# Sheet5.net
KiCad netlist of a schematic drawn in Altium Designer
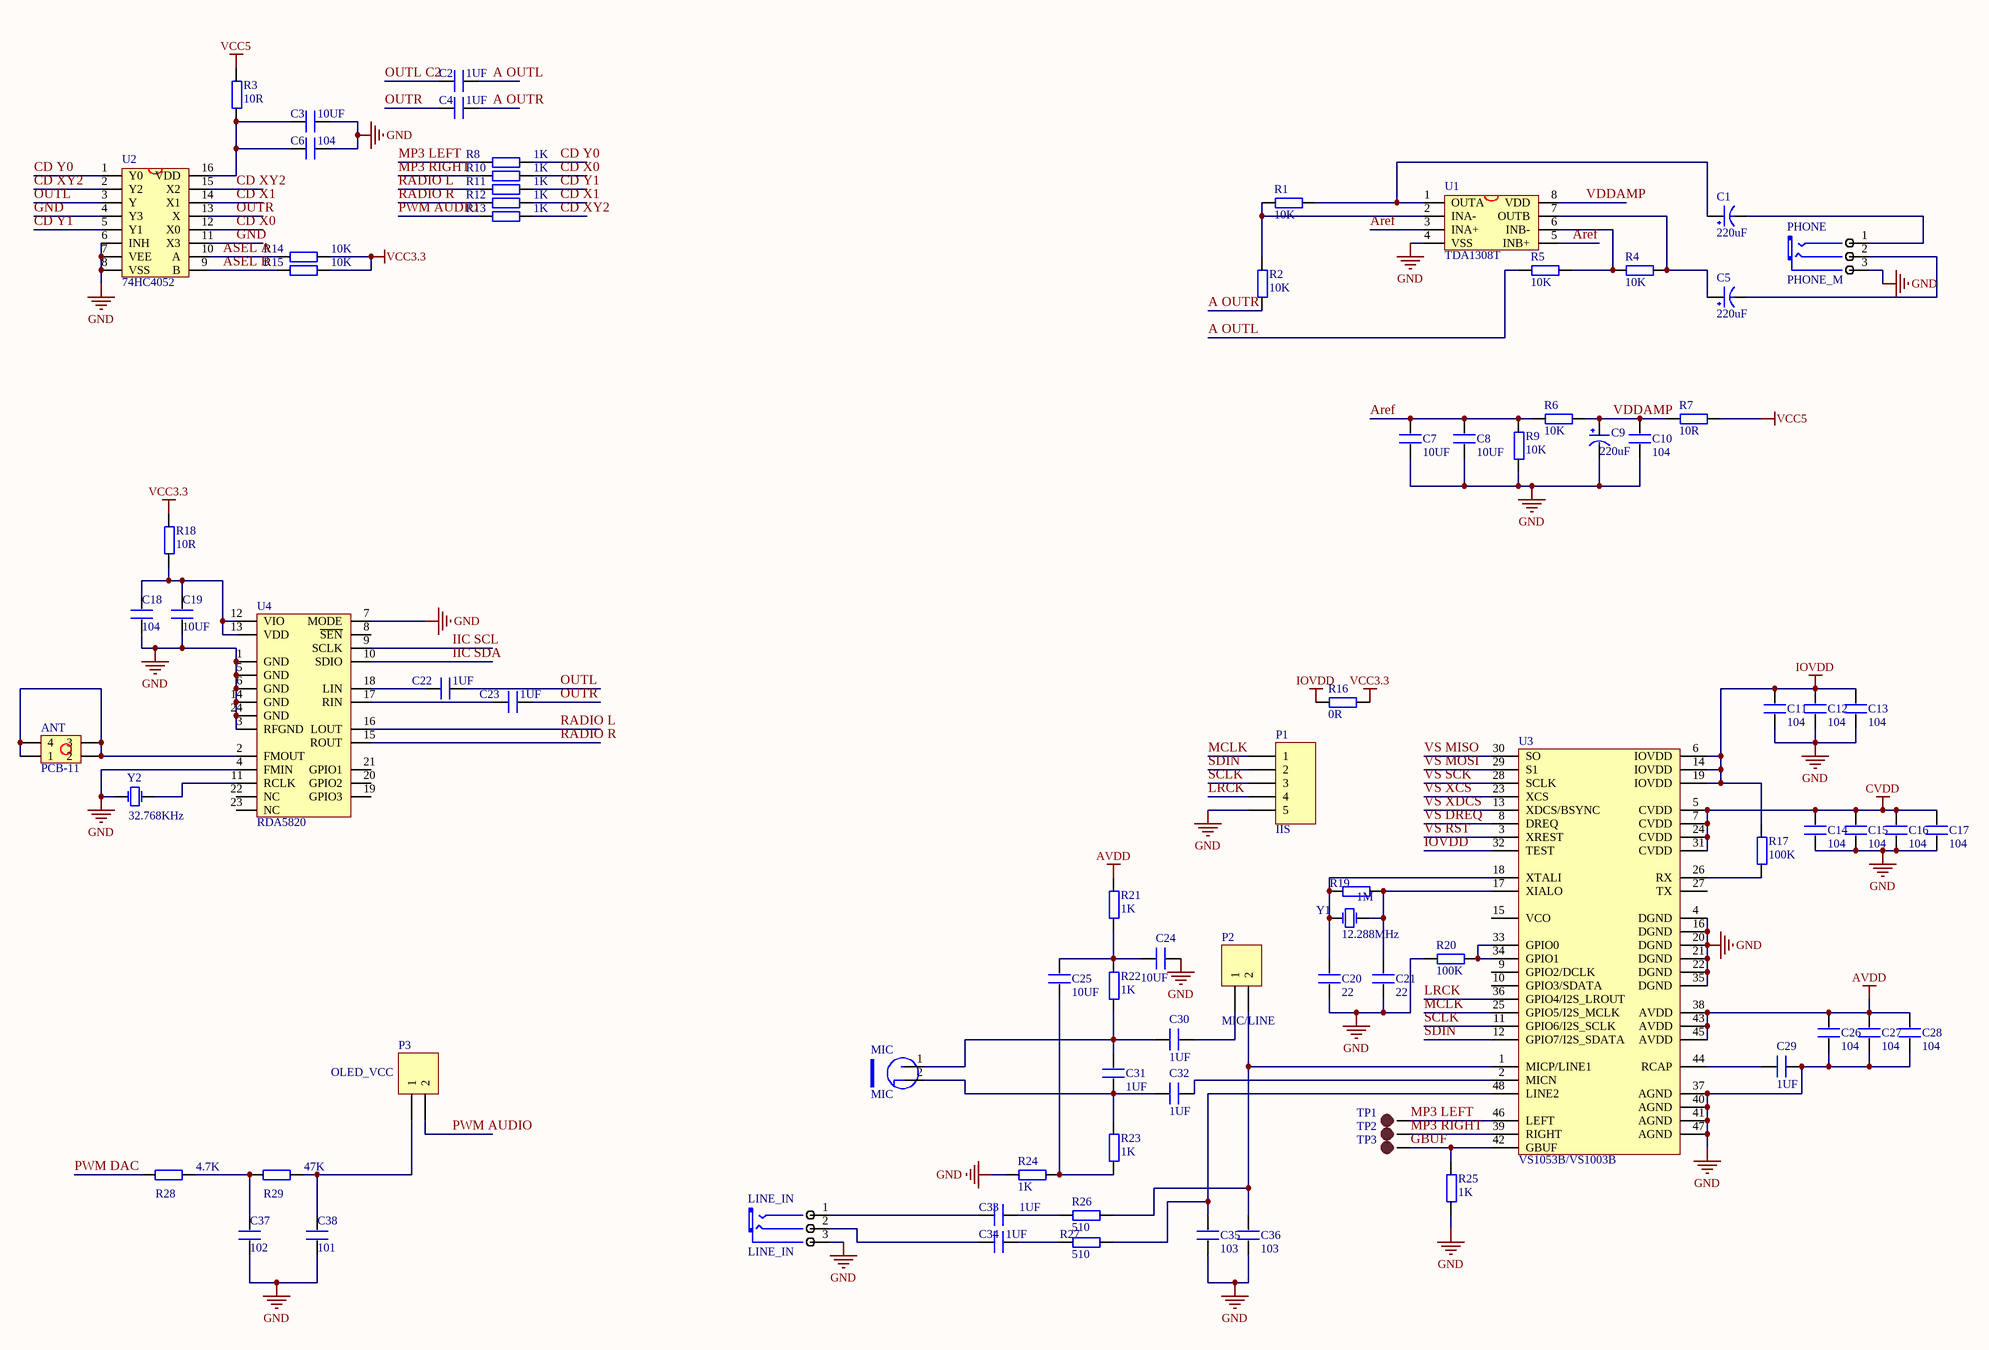
[diagram p0: Sheet5.SchDoc]

(export (version "E")
  (design (tool "Eeschema 10.0.6"))
  (components
    (comp (ref "ANT")
      (value "PCB-11")
      (footprint "PCB-11")
      (description "PCB接线端子")
      (libsource (lib "战舰STM32开发板底板封装库") (part "PCB-11"))
    )
    (comp (ref "C1") (value "220uF") (footprint "CC6.56.5") (libsource (lib "战舰STM32开发板底板封装库") (part "CAP")))
    (comp (ref "C2") (value "1UF") (footprint "0603P") (libsource (lib "战舰STM32开发板底板封装库") (part "C")))
    (comp (ref "C3") (value "10UF") (footprint "0603P") (libsource (lib "战舰STM32开发板底板封装库") (part "C")))
    (comp (ref "C4") (value "1UF") (footprint "0603P") (libsource (lib "战舰STM32开发板底板封装库") (part "C")))
    (comp (ref "C5") (value "220uF") (footprint "CC6.56.5") (libsource (lib "战舰STM32开发板底板封装库") (part "CAP")))
    (comp (ref "C6") (value "104") (footprint "0603P") (libsource (lib "战舰STM32开发板底板封装库") (part "C")))
    (comp (ref "C7") (value "10UF") (footprint "0603P") (libsource (lib "战舰STM32开发板底板封装库") (part "C")))
    (comp (ref "C8") (value "10UF") (footprint "0603P") (libsource (lib "战舰STM32开发板底板封装库") (part "C")))
    (comp (ref "C9") (value "220uF") (footprint "CC6.56.5") (libsource (lib "") (part "CAP_1")))
    (comp (ref "C10") (value "104") (footprint "0603P") (libsource (lib "战舰STM32开发板底板封装库") (part "C")))
    (comp (ref "C11") (value "104") (footprint "0603P") (libsource (lib "战舰STM32开发板底板封装库") (part "C")))
    (comp (ref "C12") (value "104") (footprint "0603P") (libsource (lib "战舰STM32开发板底板封装库") (part "C")))
    (comp (ref "C13") (value "104") (footprint "0603P") (libsource (lib "战舰STM32开发板底板封装库") (part "C")))
    (comp (ref "C14") (value "104") (footprint "0603P") (libsource (lib "战舰STM32开发板底板封装库") (part "C")))
    (comp (ref "C15") (value "104") (footprint "0603P") (libsource (lib "战舰STM32开发板底板封装库") (part "C")))
    (comp (ref "C16") (value "104") (footprint "0603P") (libsource (lib "战舰STM32开发板底板封装库") (part "C")))
    (comp (ref "C17") (value "104") (footprint "0603P") (libsource (lib "战舰STM32开发板底板封装库") (part "C")))
    (comp (ref "C18") (value "104") (footprint "0603P") (libsource (lib "战舰STM32开发板底板封装库") (part "C")))
    (comp (ref "C19") (value "10UF") (footprint "0603P") (libsource (lib "战舰STM32开发板底板封装库") (part "C")))
    (comp (ref "C20") (value "22") (footprint "0603P") (libsource (lib "战舰STM32开发板底板封装库") (part "C")))
    (comp (ref "C21") (value "22") (footprint "0603P") (libsource (lib "战舰STM32开发板底板封装库") (part "C")))
    (comp (ref "C22") (value "1UF") (footprint "0603P") (libsource (lib "战舰STM32开发板底板封装库") (part "C")))
    (comp (ref "C23") (value "1UF") (footprint "0603P") (libsource (lib "战舰STM32开发板底板封装库") (part "C")))
    (comp (ref "C24") (value "10UF") (footprint "0603P") (libsource (lib "战舰STM32开发板底板封装库") (part "C")))
    (comp (ref "C25") (value "10UF") (footprint "0603P") (libsource (lib "战舰STM32开发板底板封装库") (part "C")))
    (comp (ref "C26") (value "104") (footprint "0603P") (libsource (lib "战舰STM32开发板底板封装库") (part "C")))
    (comp (ref "C27") (value "104") (footprint "0603P") (libsource (lib "战舰STM32开发板底板封装库") (part "C")))
    (comp (ref "C28") (value "104") (footprint "0603P") (libsource (lib "战舰STM32开发板底板封装库") (part "C")))
    (comp (ref "C29") (value "1UF") (footprint "0603P") (libsource (lib "战舰STM32开发板底板封装库") (part "C")))
    (comp (ref "C30") (value "1UF") (footprint "0603P") (libsource (lib "战舰STM32开发板底板封装库") (part "C")))
    (comp (ref "C31") (value "1UF") (footprint "0603P") (libsource (lib "战舰STM32开发板底板封装库") (part "C")))
    (comp (ref "C32") (value "1UF") (footprint "0603P") (libsource (lib "战舰STM32开发板底板封装库") (part "C")))
    (comp (ref "C33") (value "1UF") (footprint "0603P") (libsource (lib "战舰STM32开发板底板封装库") (part "C")))
    (comp (ref "C34") (value "1UF") (footprint "0603P") (libsource (lib "战舰STM32开发板底板封装库") (part "C")))
    (comp (ref "C35") (value "103") (footprint "0603P") (libsource (lib "战舰STM32开发板底板封装库") (part "C")))
    (comp (ref "C36") (value "103") (footprint "0603P") (libsource (lib "战舰STM32开发板底板封装库") (part "C")))
    (comp (ref "C37") (value "102") (footprint "0603P") (libsource (lib "战舰STM32开发板底板封装库") (part "C")))
    (comp (ref "C38") (value "101") (footprint "0603P") (libsource (lib "战舰STM32开发板底板封装库") (part "C")))
    (comp (ref "LINE_IN")
      (value "LINE_IN")
      (footprint "PHONE_ST")
      (libsource (lib "战舰STM32开发板底板封装库") (part "PHONE_M"))
    )
    (comp (ref "MIC") (value "MIC") (footprint "MIC") (libsource (lib "战舰STM32开发板底板封装库") (part "MIC")))
    (comp (ref "P1")
      (value "IIS")
      (footprint "HDR1X5")
      (description "Header, 5-Pin")
      (fields (field (name "PUBLISHER") "Altium Limited"))
      (libsource (lib "战舰STM32开发板底板封装库") (part "Header 5"))
    )
    (comp (ref "P2")
      (value "MIC/LINE")
      (footprint "HDR1X2")
      (description "Header, 2-Pin")
      (fields (field (name "PUBLISHER") "Altium Limited"))
      (libsource (lib "战舰STM32开发板底板封装库") (part "Header 2"))
    )
    (comp (ref "P3")
      (value "OLED_VCC")
      (footprint "HDR1X2")
      (description "Header, 2-Pin")
      (fields (field (name "PUBLISHER") "Altium Limited"))
      (libsource (lib "战舰STM32开发板底板封装库") (part "Header 2"))
    )
    (comp (ref "PHONE")
      (value "PHONE_M")
      (footprint "PHONE_ST")
      (libsource (lib "战舰STM32开发板底板封装库") (part "PHONE_M"))
    )
    (comp (ref "R1") (value "10K") (footprint "0603P") (libsource (lib "战舰STM32开发板底板封装库") (part "R")))
    (comp (ref "R2") (value "10K") (footprint "0603P") (libsource (lib "战舰STM32开发板底板封装库") (part "R")))
    (comp (ref "R3") (value "10R") (footprint "0603P") (libsource (lib "战舰STM32开发板底板封装库") (part "R")))
    (comp (ref "R4") (value "10K") (footprint "0603P") (libsource (lib "战舰STM32开发板底板封装库") (part "R")))
    (comp (ref "R5") (value "10K") (footprint "0603P") (libsource (lib "战舰STM32开发板底板封装库") (part "R")))
    (comp (ref "R6") (value "10K") (footprint "0603P") (libsource (lib "战舰STM32开发板底板封装库") (part "R")))
    (comp (ref "R7") (value "10R") (footprint "0603P") (libsource (lib "战舰STM32开发板底板封装库") (part "R")))
    (comp (ref "R8") (value "1K") (footprint "0603P") (libsource (lib "战舰STM32开发板底板封装库") (part "R")))
    (comp (ref "R9") (value "10K") (footprint "0603P") (libsource (lib "战舰STM32开发板底板封装库") (part "R")))
    (comp (ref "R10") (value "1K") (footprint "0603P") (libsource (lib "战舰STM32开发板底板封装库") (part "R")))
    (comp (ref "R11") (value "1K") (footprint "0603P") (libsource (lib "战舰STM32开发板底板封装库") (part "R")))
    (comp (ref "R12") (value "1K") (footprint "0603P") (libsource (lib "战舰STM32开发板底板封装库") (part "R")))
    (comp (ref "R13") (value "1K") (footprint "0603P") (libsource (lib "战舰STM32开发板底板封装库") (part "R")))
    (comp (ref "R14") (value "10K") (footprint "0603P") (libsource (lib "战舰STM32开发板底板封装库") (part "R")))
    (comp (ref "R15") (value "10K") (footprint "0603P") (libsource (lib "战舰STM32开发板底板封装库") (part "R")))
    (comp (ref "R16") (value "0R") (footprint "0603P") (libsource (lib "战舰STM32开发板底板封装库") (part "R")))
    (comp (ref "R17") (value "100K") (footprint "0603P") (libsource (lib "战舰STM32开发板底板封装库") (part "R")))
    (comp (ref "R18") (value "10R") (footprint "0603P") (libsource (lib "战舰STM32开发板底板封装库") (part "R")))
    (comp (ref "R19") (value "1M") (footprint "0603P") (libsource (lib "战舰STM32开发板底板封装库") (part "R")))
    (comp (ref "R20") (value "100K") (footprint "0603P") (libsource (lib "战舰STM32开发板底板封装库") (part "R")))
    (comp (ref "R21") (value "1K") (footprint "0603P") (libsource (lib "战舰STM32开发板底板封装库") (part "R")))
    (comp (ref "R22") (value "1K") (footprint "0603P") (libsource (lib "战舰STM32开发板底板封装库") (part "R")))
    (comp (ref "R23") (value "1K") (footprint "0603P") (libsource (lib "战舰STM32开发板底板封装库") (part "R")))
    (comp (ref "R24") (value "1K") (footprint "0603P") (libsource (lib "战舰STM32开发板底板封装库") (part "R")))
    (comp (ref "R25") (value "1K") (footprint "0603P") (libsource (lib "战舰STM32开发板底板封装库") (part "R")))
    (comp (ref "R26") (value "510") (footprint "0603P") (libsource (lib "战舰STM32开发板底板封装库") (part "R")))
    (comp (ref "R27") (value "510") (footprint "0603P") (libsource (lib "战舰STM32开发板底板封装库") (part "R")))
    (comp (ref "R28") (value "4.7K") (footprint "0603P") (libsource (lib "战舰STM32开发板底板封装库") (part "R")))
    (comp (ref "R29") (value "47K") (footprint "0603P") (libsource (lib "战舰STM32开发板底板封装库") (part "R")))
    (comp (ref "TP1")
      (value "TEST POINT")
      (footprint "TP-1.5")
      (description "测试点")
      (libsource (lib "战舰STM32开发板底板封装库") (part "TEST-POINT"))
    )
    (comp (ref "TP2")
      (value "TEST POINT")
      (footprint "TP-1.5")
      (description "测试点")
      (libsource (lib "战舰STM32开发板底板封装库") (part "TEST-POINT"))
    )
    (comp (ref "TP3")
      (value "TEST POINT")
      (footprint "TP-1.5")
      (description "测试点")
      (libsource (lib "战舰STM32开发板底板封装库") (part "TEST-POINT"))
    )
    (comp (ref "U1")
      (value "TDA1308T")
      (footprint "SOP-8")
      (libsource (lib "战舰STM32开发板底板封装库") (part "TDA1308"))
    )
    (comp (ref "U2")
      (value "74HC4052")
      (footprint "SOP16M")
      (libsource (lib "战舰STM32开发板底板封装库") (part "CD4052"))
    )
    (comp (ref "U3")
      (value "VS1053B/VS1003B")
      (footprint "mTQFP48")
      (libsource (lib "战舰STM32开发板底板封装库") (part "VS1053"))
    )
    (comp (ref "U4")
      (value "RDA5820")
      (footprint "QFN24")
      (libsource (lib "战舰STM32开发板底板封装库") (part "RDA5820"))
    )
    (comp (ref "Y1")
      (value "12.288MHz")
      (footprint "XTAL_US")
      (description "Crystal Oscillator")
      (fields (field (name "PUBLISHER") "Altium Limited"))
      (libsource (lib "战舰STM32开发板底板封装库") (part "XTAL_2"))
    )
    (comp (ref "Y2")
      (value "32.768KHz")
      (footprint "XTAL32")
      (description "32.768K")
      (fields (field (name "PUBLISHER") "Altium Limited"))
      (libsource (lib "战舰STM32开发板底板封装库") (part "XTAL_3"))
    )
  )
  (nets
    (net (code "1") (name "/A OUTL") (class "Default")
      (node (ref "C2") (pin "2") (pintype "passive"))
      (node (ref "R5") (pin "1") (pintype "passive"))
    )
    (net (code "2") (name "/A OUTR") (class "Default")
      (node (ref "C4") (pin "2") (pintype "passive"))
      (node (ref "R2") (pin "1") (pintype "passive"))
    )
    (net (code "3") (name "/ASEL A") (class "Default")
      (node (ref "R14") (pin "1") (pintype "passive"))
      (node (ref "U2") (pin "10") (pinfunction "A_10") (pintype "passive"))
    )
    (net (code "4") (name "/ASEL B") (class "Default")
      (node (ref "R15") (pin "1") (pintype "passive"))
      (node (ref "U2") (pin "9") (pinfunction "B_9") (pintype "passive"))
    )
    (net (code "5") (name "/Aref") (class "Default")
      (node (ref "C7") (pin "2") (pintype "passive"))
      (node (ref "C8") (pin "2") (pintype "passive"))
      (node (ref "R6") (pin "1") (pintype "passive"))
      (node (ref "R9") (pin "2") (pintype "passive"))
      (node (ref "U1") (pin "3") (pinfunction "INA+_3") (pintype "passive"))
      (node (ref "U1") (pin "5") (pinfunction "INB+_5") (pintype "passive"))
    )
    (net (code "6") (name "/CD X0") (class "Default")
      (node (ref "R10") (pin "2") (pintype "passive"))
      (node (ref "U2") (pin "12") (pinfunction "X0_12") (pintype "passive"))
    )
    (net (code "7") (name "/CD X1") (class "Default")
      (node (ref "R12") (pin "2") (pintype "passive"))
      (node (ref "U2") (pin "14") (pinfunction "X1_14") (pintype "passive"))
    )
    (net (code "8") (name "/CD XY2") (class "Default")
      (node (ref "R13") (pin "2") (pintype "passive"))
      (node (ref "U2") (pin "15") (pinfunction "X2_15") (pintype "passive"))
      (node (ref "U2") (pin "2") (pinfunction "Y2_2") (pintype "passive"))
    )
    (net (code "9") (name "/CD Y0") (class "Default")
      (node (ref "R8") (pin "2") (pintype "passive"))
      (node (ref "U2") (pin "1") (pinfunction "Y0_1") (pintype "passive"))
    )
    (net (code "10") (name "/CD Y1") (class "Default")
      (node (ref "R11") (pin "2") (pintype "passive"))
      (node (ref "U2") (pin "5") (pinfunction "Y1_5") (pintype "passive"))
    )
    (net (code "11") (name "/GBUF") (class "Default")
      (node (ref "R25") (pin "2") (pintype "passive"))
      (node (ref "TP3") (pin "1") (pinfunction "1_1") (pintype "passive"))
      (node (ref "U3") (pin "42") (pinfunction "GBUF_42") (pintype "passive"))
    )
    (net (code "12") (name "/IIC SCL") (class "Default")
      (node (ref "U4") (pin "9") (pinfunction "SCLK_9") (pintype "passive"))
    )
    (net (code "13") (name "/IIC SDA") (class "Default")
      (node (ref "U4") (pin "10") (pinfunction "SDIO_10") (pintype "passive"))
    )
    (net (code "14") (name "/LRCK") (class "Default")
      (node (ref "P1") (pin "4") (pinfunction "4_4") (pintype "passive"))
      (node (ref "U3") (pin "36") (pinfunction "GPIO4/I2S_LROUT_36") (pintype "passive"))
    )
    (net (code "15") (name "/MCLK") (class "Default")
      (node (ref "P1") (pin "1") (pinfunction "1_1") (pintype "passive"))
      (node (ref "U3") (pin "25") (pinfunction "GPIO5/I2S_MCLK_25") (pintype "passive"))
    )
    (net (code "16") (name "/MP3 LEFT") (class "Default")
      (node (ref "R8") (pin "1") (pintype "passive"))
      (node (ref "TP1") (pin "1") (pinfunction "1_1") (pintype "passive"))
      (node (ref "U3") (pin "46") (pinfunction "LEFT_46") (pintype "passive"))
    )
    (net (code "17") (name "/MP3 RIGHT") (class "Default")
      (node (ref "R10") (pin "1") (pintype "passive"))
      (node (ref "TP2") (pin "1") (pinfunction "1_1") (pintype "passive"))
      (node (ref "U3") (pin "39") (pinfunction "RIGHT_39") (pintype "passive"))
    )
    (net (code "18") (name "/OUTL") (class "Default")
      (node (ref "C22") (pin "1") (pintype "passive"))
      (node (ref "U2") (pin "3") (pinfunction "Y_3") (pintype "passive"))
    )
    (net (code "19") (name "/OUTL C2") (class "Default") (node (ref "C2") (pin "1") (pintype "passive")))
    (net (code "20") (name "/OUTR") (class "Default")
      (node (ref "C23") (pin "1") (pintype "passive"))
      (node (ref "C4") (pin "1") (pintype "passive"))
      (node (ref "U2") (pin "13") (pinfunction "X_13") (pintype "passive"))
    )
    (net (code "21") (name "/PWM AUDIO") (class "Default")
      (node (ref "P3") (pin "2") (pinfunction "2_2") (pintype "passive"))
      (node (ref "R13") (pin "1") (pintype "passive"))
    )
    (net (code "22") (name "/PWM DAC") (class "Default") (node (ref "R28") (pin "1") (pintype "passive")))
    (net (code "23") (name "/RADIO L") (class "Default")
      (node (ref "R11") (pin "1") (pintype "passive"))
      (node (ref "U4") (pin "16") (pinfunction "LOUT_16") (pintype "passive"))
    )
    (net (code "24") (name "/RADIO R") (class "Default")
      (node (ref "R12") (pin "1") (pintype "passive"))
      (node (ref "U4") (pin "15") (pinfunction "ROUT_15") (pintype "passive"))
    )
    (net (code "25") (name "/SCLK") (class "Default")
      (node (ref "P1") (pin "3") (pinfunction "3_3") (pintype "passive"))
      (node (ref "U3") (pin "11") (pinfunction "GPIO6/I2S_SCLK_11") (pintype "passive"))
    )
    (net (code "26") (name "/SDIN") (class "Default")
      (node (ref "P1") (pin "2") (pinfunction "2_2") (pintype "passive"))
      (node (ref "U3") (pin "12") (pinfunction "GPIO7/I2S_SDATA_12") (pintype "passive"))
    )
    (net (code "27") (name "/VDDAMP") (class "Default")
      (node (ref "C10") (pin "2") (pintype "passive"))
      (node (ref "C9") (pin "1") (pinfunction "VCC_1") (pintype "passive"))
      (node (ref "R6") (pin "2") (pintype "passive"))
      (node (ref "R7") (pin "1") (pintype "passive"))
      (node (ref "U1") (pin "8") (pinfunction "VDD_8") (pintype "passive"))
    )
    (net (code "28") (name "/VS DREQ") (class "Default")
      (node (ref "U3") (pin "8") (pinfunction "DREQ_8") (pintype "passive"))
    )
    (net (code "29") (name "/VS MISO") (class "Default")
      (node (ref "U3") (pin "30") (pinfunction "SO_30") (pintype "passive"))
    )
    (net (code "30") (name "/VS MOSI") (class "Default")
      (node (ref "U3") (pin "29") (pinfunction "S1_29") (pintype "passive"))
    )
    (net (code "31") (name "/VS RST") (class "Default")
      (node (ref "U3") (pin "3") (pinfunction "XREST_3") (pintype "passive"))
    )
    (net (code "32") (name "/VS SCK") (class "Default")
      (node (ref "U3") (pin "28") (pinfunction "SCLK_28") (pintype "passive"))
    )
    (net (code "33") (name "/VS XCS") (class "Default")
      (node (ref "U3") (pin "23") (pinfunction "XCS_23") (pintype "passive"))
    )
    (net (code "34") (name "/VS XDCS") (class "Default")
      (node (ref "U3") (pin "13") (pinfunction "XDCS/BSYNC_13") (pintype "passive"))
    )
    (net (code "35") (name "AVDD") (class "Default")
      (node (ref "C26") (pin "2") (pintype "passive"))
      (node (ref "C27") (pin "2") (pintype "passive"))
      (node (ref "C28") (pin "2") (pintype "passive"))
      (node (ref "R21") (pin "2") (pintype "passive"))
      (node (ref "U3") (pin "38") (pinfunction "AVDD_38") (pintype "passive"))
      (node (ref "U3") (pin "43") (pinfunction "AVDD_43") (pintype "passive"))
      (node (ref "U3") (pin "45") (pinfunction "AVDD_45") (pintype "passive"))
    )
    (net (code "36") (name "CVDD") (class "Default")
      (node (ref "C14") (pin "2") (pintype "passive"))
      (node (ref "C15") (pin "2") (pintype "passive"))
      (node (ref "C16") (pin "2") (pintype "passive"))
      (node (ref "C17") (pin "2") (pintype "passive"))
      (node (ref "U3") (pin "24") (pinfunction "CVDD_24") (pintype "passive"))
      (node (ref "U3") (pin "31") (pinfunction "CVDD_31") (pintype "passive"))
      (node (ref "U3") (pin "5") (pinfunction "CVDD_5") (pintype "passive"))
      (node (ref "U3") (pin "7") (pinfunction "CVDD_7") (pintype "passive"))
    )
    (net (code "37") (name "GND") (class "Default")
      (node (ref "C10") (pin "1") (pintype "passive"))
      (node (ref "C11") (pin "1") (pintype "passive"))
      (node (ref "C12") (pin "1") (pintype "passive"))
      (node (ref "C13") (pin "1") (pintype "passive"))
      (node (ref "C14") (pin "1") (pintype "passive"))
      (node (ref "C15") (pin "1") (pintype "passive"))
      (node (ref "C16") (pin "1") (pintype "passive"))
      (node (ref "C17") (pin "1") (pintype "passive"))
      (node (ref "C18") (pin "1") (pintype "passive"))
      (node (ref "C19") (pin "1") (pintype "passive"))
      (node (ref "C20") (pin "1") (pintype "passive"))
      (node (ref "C21") (pin "1") (pintype "passive"))
      (node (ref "C24") (pin "1") (pintype "passive"))
      (node (ref "C26") (pin "1") (pintype "passive"))
      (node (ref "C27") (pin "1") (pintype "passive"))
      (node (ref "C28") (pin "1") (pintype "passive"))
      (node (ref "C29") (pin "2") (pintype "passive"))
      (node (ref "C3") (pin "2") (pintype "passive"))
      (node (ref "C35") (pin "1") (pintype "passive"))
      (node (ref "C36") (pin "1") (pintype "passive"))
      (node (ref "C37") (pin "1") (pintype "passive"))
      (node (ref "C38") (pin "1") (pintype "passive"))
      (node (ref "C6") (pin "2") (pintype "passive"))
      (node (ref "C7") (pin "1") (pintype "passive"))
      (node (ref "C8") (pin "1") (pintype "passive"))
      (node (ref "C9") (pin "2") (pinfunction "GND_2") (pintype "passive"))
      (node (ref "LINE_IN") (pin "3") (pinfunction "COM_3") (pintype "passive"))
      (node (ref "P1") (pin "5") (pinfunction "5_5") (pintype "passive"))
      (node (ref "PHONE") (pin "3") (pinfunction "COM_3") (pintype "passive"))
      (node (ref "R20") (pin "1") (pintype "passive"))
      (node (ref "R24") (pin "1") (pintype "passive"))
      (node (ref "R25") (pin "1") (pintype "passive"))
      (node (ref "R9") (pin "1") (pintype "passive"))
      (node (ref "U1") (pin "4") (pinfunction "VSS_4") (pintype "passive"))
      (node (ref "U2") (pin "11") (pinfunction "X3_11") (pintype "passive"))
      (node (ref "U2") (pin "4") (pinfunction "Y3_4") (pintype "passive"))
      (node (ref "U2") (pin "6") (pinfunction "INH_6") (pintype "passive"))
      (node (ref "U2") (pin "7") (pinfunction "VEE_7") (pintype "passive"))
      (node (ref "U2") (pin "8") (pinfunction "VSS_8") (pintype "passive"))
      (node (ref "U3") (pin "16") (pinfunction "DGND_16") (pintype "passive"))
      (node (ref "U3") (pin "20") (pinfunction "DGND_20") (pintype "passive"))
      (node (ref "U3") (pin "21") (pinfunction "DGND_21") (pintype "passive"))
      (node (ref "U3") (pin "22") (pinfunction "DGND_22") (pintype "passive"))
      (node (ref "U3") (pin "35") (pinfunction "DGND_35") (pintype "passive"))
      (node (ref "U3") (pin "37") (pinfunction "AGND_37") (pintype "passive"))
      (node (ref "U3") (pin "4") (pinfunction "DGND_4") (pintype "passive"))
      (node (ref "U3") (pin "40") (pinfunction "AGND_40") (pintype "passive"))
      (node (ref "U3") (pin "41") (pinfunction "AGND_41") (pintype "passive"))
      (node (ref "U3") (pin "47") (pinfunction "AGND_47") (pintype "passive"))
      (node (ref "U4") (pin "1") (pinfunction "GND_1") (pintype "passive"))
      (node (ref "U4") (pin "14") (pinfunction "GND_14") (pintype "passive"))
      (node (ref "U4") (pin "24") (pinfunction "GND_24") (pintype "passive"))
      (node (ref "U4") (pin "3") (pinfunction "RFGND_3") (pintype "passive"))
      (node (ref "U4") (pin "4") (pinfunction "FMIN_4") (pintype "passive"))
      (node (ref "U4") (pin "5") (pinfunction "GND_5") (pintype "passive"))
      (node (ref "U4") (pin "6") (pinfunction "GND_6") (pintype "passive"))
      (node (ref "U4") (pin "7") (pinfunction "MODE_7") (pintype "passive"))
      (node (ref "Y2") (pin "1") (pinfunction "OSC1_1") (pintype "passive"))
    )
    (net (code "38") (name "IOVDD") (class "Default")
      (node (ref "C11") (pin "2") (pintype "passive"))
      (node (ref "C12") (pin "2") (pintype "passive"))
      (node (ref "C13") (pin "2") (pintype "passive"))
      (node (ref "R16") (pin "1") (pintype "passive"))
      (node (ref "R17") (pin "2") (pintype "passive"))
      (node (ref "U3") (pin "14") (pinfunction "IOVDD_14") (pintype "passive"))
      (node (ref "U3") (pin "19") (pinfunction "IOVDD_19") (pintype "passive"))
      (node (ref "U3") (pin "32") (pinfunction "TEST_32") (pintype "passive"))
      (node (ref "U3") (pin "6") (pinfunction "IOVDD_6") (pintype "passive"))
    )
    (net (code "39") (name "Net-(C1-GND)") (class "Default")
      (node (ref "C1") (pin "2") (pinfunction "GND_2") (pintype "passive"))
      (node (ref "PHONE") (pin "1") (pinfunction "CHL_1") (pintype "passive"))
    )
    (net (code "40") (name "Net-(C1-VCC)") (class "Default")
      (node (ref "C1") (pin "1") (pinfunction "VCC_1") (pintype "passive"))
      (node (ref "R1") (pin "2") (pintype "passive"))
      (node (ref "U1") (pin "1") (pinfunction "OUTA_1") (pintype "passive"))
    )
    (net (code "41") (name "Net-(C5-GND)") (class "Default")
      (node (ref "C5") (pin "2") (pinfunction "GND_2") (pintype "passive"))
      (node (ref "PHONE") (pin "2") (pinfunction "CHR_2") (pintype "passive"))
    )
    (net (code "42") (name "Net-(C5-VCC)") (class "Default")
      (node (ref "C5") (pin "1") (pinfunction "VCC_1") (pintype "passive"))
      (node (ref "R4") (pin "2") (pintype "passive"))
      (node (ref "U1") (pin "7") (pinfunction "OUTB_7") (pintype "passive"))
    )
    (net (code "43") (name "Net-(C24-Pad2)") (class "Default")
      (node (ref "C24") (pin "2") (pintype "passive"))
      (node (ref "C25") (pin "2") (pintype "passive"))
      (node (ref "R21") (pin "1") (pintype "passive"))
      (node (ref "R22") (pin "2") (pintype "passive"))
    )
    (net (code "44") (name "Net-(C25-Pad1)") (class "Default")
      (node (ref "C25") (pin "1") (pintype "passive"))
      (node (ref "R23") (pin "1") (pintype "passive"))
      (node (ref "R24") (pin "2") (pintype "passive"))
    )
    (net (code "45") (name "Net-(C30-Pad2)") (class "Default")
      (node (ref "C30") (pin "2") (pintype "passive"))
      (node (ref "P2") (pin "1") (pinfunction "1_1") (pintype "passive"))
    )
    (net (code "46") (name "Net-(C33-Pad2)") (class "Default")
      (node (ref "C33") (pin "2") (pintype "passive"))
      (node (ref "R26") (pin "1") (pintype "passive"))
    )
    (net (code "47") (name "Net-(C34-Pad2)") (class "Default")
      (node (ref "C34") (pin "2") (pintype "passive"))
      (node (ref "R27") (pin "1") (pintype "passive"))
    )
    (net (code "48") (name "Net-(C37-Pad2)") (class "Default")
      (node (ref "C37") (pin "2") (pintype "passive"))
      (node (ref "R28") (pin "2") (pintype "passive"))
      (node (ref "R29") (pin "1") (pintype "passive"))
    )
    (net (code "49") (name "Net-(C38-Pad2)") (class "Default")
      (node (ref "C38") (pin "2") (pintype "passive"))
      (node (ref "P3") (pin "1") (pinfunction "1_1") (pintype "passive"))
      (node (ref "R29") (pin "2") (pintype "passive"))
    )
    (net (code "50") (name "Net-(LINE_IN-CHL)") (class "Default")
      (node (ref "C33") (pin "1") (pintype "passive"))
      (node (ref "LINE_IN") (pin "1") (pinfunction "CHL_1") (pintype "passive"))
    )
    (net (code "51") (name "Net-(LINE_IN-CHR)") (class "Default")
      (node (ref "C34") (pin "1") (pintype "passive"))
      (node (ref "LINE_IN") (pin "2") (pinfunction "CHR_2") (pintype "passive"))
    )
    (net (code "52") (name "Net-(MIC-GND)") (class "Default")
      (node (ref "C31") (pin "1") (pintype "passive"))
      (node (ref "C32") (pin "1") (pintype "passive"))
      (node (ref "MIC") (pin "2") (pinfunction "GND_2") (pintype "passive"))
      (node (ref "R23") (pin "2") (pintype "passive"))
    )
    (net (code "53") (name "Net-(MIC-VCC)") (class "Default")
      (node (ref "C30") (pin "1") (pintype "passive"))
      (node (ref "C31") (pin "2") (pintype "passive"))
      (node (ref "MIC") (pin "1") (pinfunction "VCC_1") (pintype "passive"))
      (node (ref "R22") (pin "1") (pintype "passive"))
    )
    (net (code "54") (name "Net-(U1-INA-)") (class "Default")
      (node (ref "R1") (pin "1") (pintype "passive"))
      (node (ref "R2") (pin "2") (pintype "passive"))
      (node (ref "U1") (pin "2") (pinfunction "INA-_2") (pintype "passive"))
    )
    (net (code "55") (name "Net-(U1-INB-)") (class "Default")
      (node (ref "R4") (pin "1") (pintype "passive"))
      (node (ref "R5") (pin "2") (pintype "passive"))
      (node (ref "U1") (pin "6") (pinfunction "INB-_6") (pintype "passive"))
    )
    (net (code "56") (name "Net-(U2-VDD)") (class "Default")
      (node (ref "C3") (pin "1") (pintype "passive"))
      (node (ref "C6") (pin "1") (pintype "passive"))
      (node (ref "R3") (pin "1") (pintype "passive"))
      (node (ref "U2") (pin "16") (pinfunction "VDD_16") (pintype "passive"))
    )
    (net (code "57") (name "Net-(U3-GPIO0)") (class "Default")
      (node (ref "R20") (pin "2") (pintype "passive"))
      (node (ref "U3") (pin "33") (pinfunction "GPIO0_33") (pintype "passive"))
      (node (ref "U3") (pin "34") (pinfunction "GPIO1_34") (pintype "passive"))
    )
    (net (code "58") (name "Net-(U3-LINE2)") (class "Default")
      (node (ref "C35") (pin "2") (pintype "passive"))
      (node (ref "R27") (pin "2") (pintype "passive"))
      (node (ref "U3") (pin "48") (pinfunction "LINE2_48") (pintype "passive"))
    )
    (net (code "59") (name "Net-(U3-MICN)") (class "Default")
      (node (ref "C32") (pin "2") (pintype "passive"))
      (node (ref "U3") (pin "2") (pinfunction "MICN_2") (pintype "passive"))
    )
    (net (code "60") (name "Net-(U3-MICP{slash}LINE1)") (class "Default")
      (node (ref "C36") (pin "2") (pintype "passive"))
      (node (ref "P2") (pin "2") (pinfunction "2_2") (pintype "passive"))
      (node (ref "R26") (pin "2") (pintype "passive"))
      (node (ref "U3") (pin "1") (pinfunction "MICP/LINE1_1") (pintype "passive"))
    )
    (net (code "61") (name "Net-(U3-RCAP)") (class "Default")
      (node (ref "C29") (pin "1") (pintype "passive"))
      (node (ref "U3") (pin "44") (pinfunction "RCAP_44") (pintype "passive"))
    )
    (net (code "62") (name "Net-(U3-RX)") (class "Default")
      (node (ref "R17") (pin "1") (pintype "passive"))
      (node (ref "U3") (pin "26") (pinfunction "RX_26") (pintype "passive"))
    )
    (net (code "63") (name "Net-(U3-XIALO)") (class "Default")
      (node (ref "C21") (pin "2") (pintype "passive"))
      (node (ref "R19") (pin "2") (pintype "passive"))
      (node (ref "U3") (pin "17") (pinfunction "XIALO_17") (pintype "passive"))
      (node (ref "Y1") (pin "2") (pinfunction "OSC2_2") (pintype "passive"))
    )
    (net (code "64") (name "Net-(U3-XTALI)") (class "Default")
      (node (ref "C20") (pin "2") (pintype "passive"))
      (node (ref "R19") (pin "1") (pintype "passive"))
      (node (ref "U3") (pin "18") (pinfunction "XTALI_18") (pintype "passive"))
      (node (ref "Y1") (pin "1") (pinfunction "OSC1_1") (pintype "passive"))
    )
    (net (code "65") (name "Net-(U4-FMOUT)") (class "Default")
      (node (ref "ANT") (pin "1") (pinfunction "1_1") (pintype "passive"))
      (node (ref "ANT") (pin "2") (pinfunction "2_2") (pintype "passive"))
      (node (ref "ANT") (pin "3") (pinfunction "3_3") (pintype "passive"))
      (node (ref "ANT") (pin "4") (pinfunction "4_4") (pintype "passive"))
      (node (ref "U4") (pin "2") (pinfunction "FMOUT_2") (pintype "passive"))
    )
    (net (code "66") (name "Net-(U4-LIN)") (class "Default")
      (node (ref "C22") (pin "2") (pintype "passive"))
      (node (ref "U4") (pin "18") (pinfunction "LIN_18") (pintype "passive"))
    )
    (net (code "67") (name "Net-(U4-RCLK)") (class "Default")
      (node (ref "U4") (pin "11") (pinfunction "RCLK_11") (pintype "passive"))
      (node (ref "Y2") (pin "2") (pinfunction "OSC2_2") (pintype "passive"))
    )
    (net (code "68") (name "Net-(U4-RIN)") (class "Default")
      (node (ref "C23") (pin "2") (pintype "passive"))
      (node (ref "U4") (pin "17") (pinfunction "RIN_17") (pintype "passive"))
    )
    (net (code "69") (name "Net-(U4-VDD)") (class "Default")
      (node (ref "C18") (pin "2") (pintype "passive"))
      (node (ref "C19") (pin "2") (pintype "passive"))
      (node (ref "R18") (pin "1") (pintype "passive"))
      (node (ref "U4") (pin "12") (pinfunction "VIO_12") (pintype "passive"))
      (node (ref "U4") (pin "13") (pinfunction "VDD_13") (pintype "passive"))
    )
    (net (code "70") (name "VCC3.3") (class "Default")
      (node (ref "R14") (pin "2") (pintype "passive"))
      (node (ref "R15") (pin "2") (pintype "passive"))
      (node (ref "R16") (pin "2") (pintype "passive"))
      (node (ref "R18") (pin "2") (pintype "passive"))
    )
    (net (code "71") (name "VCC5") (class "Default")
      (node (ref "R3") (pin "2") (pintype "passive"))
      (node (ref "R7") (pin "2") (pintype "passive"))
    )
    (net (code "72") (name "unconnected-(U3-GPIO2{slash}DCLK-Pad9)") (class "Default")
      (node (ref "U3") (pin "9") (pinfunction "GPIO2/DCLK_9") (pintype "passive"))
    )
    (net (code "73") (name "unconnected-(U3-GPIO3{slash}SDATA-Pad10)") (class "Default")
      (node (ref "U3") (pin "10") (pinfunction "GPIO3/SDATA_10") (pintype "passive"))
    )
    (net (code "74") (name "unconnected-(U3-TX-Pad27)") (class "Default")
      (node (ref "U3") (pin "27") (pinfunction "TX_27") (pintype "passive"))
    )
    (net (code "75") (name "unconnected-(U3-VCO-Pad15)") (class "Default")
      (node (ref "U3") (pin "15") (pinfunction "VCO_15") (pintype "passive"))
    )
    (net (code "76") (name "unconnected-(U4-GPIO1-Pad21)") (class "Default")
      (node (ref "U4") (pin "21") (pinfunction "GPIO1_21") (pintype "passive"))
    )
    (net (code "77") (name "unconnected-(U4-GPIO2-Pad20)") (class "Default")
      (node (ref "U4") (pin "20") (pinfunction "GPIO2_20") (pintype "passive"))
    )
    (net (code "78") (name "unconnected-(U4-GPIO3-Pad19)") (class "Default")
      (node (ref "U4") (pin "19") (pinfunction "GPIO3_19") (pintype "passive"))
    )
    (net (code "79") (name "unconnected-(U4-NC-Pad22)") (class "Default")
      (node (ref "U4") (pin "22") (pinfunction "NC_22") (pintype "passive"))
    )
    (net (code "80") (name "unconnected-(U4-NC-Pad23)") (class "Default")
      (node (ref "U4") (pin "23") (pinfunction "NC_23") (pintype "passive"))
    )
    (net (code "81") (name "unconnected-(U4-~{SEN}-Pad8)") (class "Default")
      (node (ref "U4") (pin "8") (pinfunction "~{SEN}_8") (pintype "passive"))
    )
  )
)
